# connectors_headers_LEDs.net
KiCad netlist of a schematic drawn in Altium Designer
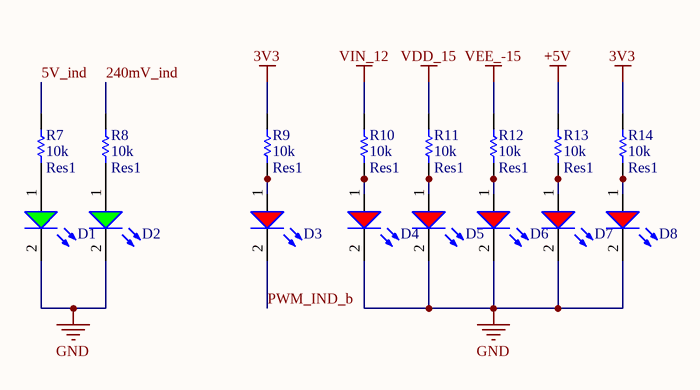
[diagram p0: connectors_headers_LEDs.SchDoc]

(export (version "E")
  (design (tool "Eeschema 10.0.6"))
  (components
    (comp (ref "D1")
      (value "Bright Green, 2.1V, 40°")
      (footprint "WL-TMRC_D3.95H5.3")
      (description "WL-TMRC Mono-color Round Color, THT, D3.95 x H5.3mm, Bright Green, 2.1V, 40°")
      (fields
        (field (name "MANUFACTURER PART NUMBER") "151031VS04000")
        (field (name "MANUFACTURER") "Wurth Elektronik")
      )
      (libsource (lib "Altium_LED_WL-TMRC") (part "151031VS04000"))
    )
    (comp (ref "D2")
      (value "Bright Green, 2.1V, 40°")
      (footprint "WL-TMRC_D3.95H5.3")
      (description "WL-TMRC Mono-color Round Color, THT, D3.95 x H5.3mm, Bright Green, 2.1V, 40°")
      (fields
        (field (name "MANUFACTURER PART NUMBER") "151031VS04000")
        (field (name "MANUFACTURER") "Wurth Elektronik")
      )
      (libsource (lib "Altium_LED_WL-TMRC") (part "151031VS04000"))
    )
    (comp (ref "D3")
      (value "Super Red, 2V, 40°")
      (footprint "WL-TMRC_D3.95H5.3")
      (description "WL-TMRC Mono-color Round Color, THT, D3.95 x H5.3mm, Super Red, 2V, 40°")
      (fields
        (field (name "MANUFACTURER PART NUMBER") "151031SS04000")
        (field (name "MANUFACTURER") "Wurth Elektronik")
      )
      (libsource (lib "Altium_LED_WL-TMRC") (part "151031SS04000"))
    )
    (comp (ref "D4")
      (value "Super Red, 2V, 40°")
      (footprint "WL-TMRC_D3.95H5.3")
      (description "WL-TMRC Mono-color Round Color, THT, D3.95 x H5.3mm, Super Red, 2V, 40°")
      (fields
        (field (name "MANUFACTURER PART NUMBER") "151031SS04000")
        (field (name "MANUFACTURER") "Wurth Elektronik")
      )
      (libsource (lib "Altium_LED_WL-TMRC") (part "151031SS04000"))
    )
    (comp (ref "D5")
      (value "Super Red, 2V, 40°")
      (footprint "WL-TMRC_D3.95H5.3")
      (description "WL-TMRC Mono-color Round Color, THT, D3.95 x H5.3mm, Super Red, 2V, 40°")
      (fields
        (field (name "MANUFACTURER PART NUMBER") "151031SS04000")
        (field (name "MANUFACTURER") "Wurth Elektronik")
      )
      (libsource (lib "Altium_LED_WL-TMRC") (part "151031SS04000"))
    )
    (comp (ref "D6")
      (value "Super Red, 2V, 40°")
      (footprint "WL-TMRC_D3.95H5.3")
      (description "WL-TMRC Mono-color Round Color, THT, D3.95 x H5.3mm, Super Red, 2V, 40°")
      (fields
        (field (name "MANUFACTURER PART NUMBER") "151031SS04000")
        (field (name "MANUFACTURER") "Wurth Elektronik")
      )
      (libsource (lib "Altium_LED_WL-TMRC") (part "151031SS04000"))
    )
    (comp (ref "D7")
      (value "Super Red, 2V, 40°")
      (footprint "WL-TMRC_D3.95H5.3")
      (description "WL-TMRC Mono-color Round Color, THT, D3.95 x H5.3mm, Super Red, 2V, 40°")
      (fields
        (field (name "MANUFACTURER PART NUMBER") "151031SS04000")
        (field (name "MANUFACTURER") "Wurth Elektronik")
      )
      (libsource (lib "Altium_LED_WL-TMRC") (part "151031SS04000"))
    )
    (comp (ref "D8")
      (value "Super Red, 2V, 40°")
      (footprint "WL-TMRC_D3.95H5.3")
      (description "WL-TMRC Mono-color Round Color, THT, D3.95 x H5.3mm, Super Red, 2V, 40°")
      (fields
        (field (name "MANUFACTURER PART NUMBER") "151031SS04000")
        (field (name "MANUFACTURER") "Wurth Elektronik")
      )
      (libsource (lib "Altium_LED_WL-TMRC") (part "151031SS04000"))
    )
    (comp (ref "R7")
      (value "Res1")
      (footprint "AXIAL-0.4")
      (description "Resistor")
      (fields (field (name "ALTIUM_VALUE") "10k") (field (name "PUBLISHER") "Altium Limited"))
      (libsource (lib "Miscellaneous Devices") (part "Res1"))
    )
    (comp (ref "R8")
      (value "Res1")
      (footprint "AXIAL-0.4")
      (description "Resistor")
      (fields (field (name "ALTIUM_VALUE") "10k") (field (name "PUBLISHER") "Altium Limited"))
      (libsource (lib "Miscellaneous Devices") (part "Res1"))
    )
    (comp (ref "R9")
      (value "Res1")
      (footprint "AXIAL-0.4")
      (description "Resistor")
      (fields (field (name "ALTIUM_VALUE") "10k") (field (name "PUBLISHER") "Altium Limited"))
      (libsource (lib "Miscellaneous Devices") (part "Res1"))
    )
    (comp (ref "R10")
      (value "Res1")
      (footprint "AXIAL-0.4")
      (description "Resistor")
      (fields (field (name "ALTIUM_VALUE") "10k") (field (name "PUBLISHER") "Altium Limited"))
      (libsource (lib "Miscellaneous Devices") (part "Res1"))
    )
    (comp (ref "R11")
      (value "Res1")
      (footprint "AXIAL-0.4")
      (description "Resistor")
      (fields (field (name "ALTIUM_VALUE") "10k") (field (name "PUBLISHER") "Altium Limited"))
      (libsource (lib "Miscellaneous Devices") (part "Res1"))
    )
    (comp (ref "R12")
      (value "Res1")
      (footprint "AXIAL-0.4")
      (description "Resistor")
      (fields (field (name "ALTIUM_VALUE") "10k") (field (name "PUBLISHER") "Altium Limited"))
      (libsource (lib "Miscellaneous Devices") (part "Res1"))
    )
    (comp (ref "R13")
      (value "Res1")
      (footprint "AXIAL-0.4")
      (description "Resistor")
      (fields (field (name "ALTIUM_VALUE") "10k") (field (name "PUBLISHER") "Altium Limited"))
      (libsource (lib "Miscellaneous Devices") (part "Res1"))
    )
    (comp (ref "R14")
      (value "Res1")
      (footprint "AXIAL-0.4")
      (description "Resistor")
      (fields (field (name "ALTIUM_VALUE") "10k") (field (name "PUBLISHER") "Altium Limited"))
      (libsource (lib "Miscellaneous Devices") (part "Res1"))
    )
  )
  (nets
    (net (code "1") (name "+5V") (class "Default")
      (node (ref "R13") (pin "2") (pinfunction "2_2") (pintype "passive"))
    )
    (net (code "2") (name "/5V_ind") (class "Default")
      (node (ref "R7") (pin "2") (pinfunction "2_2") (pintype "passive"))
    )
    (net (code "3") (name "/240mV_ind") (class "Default")
      (node (ref "R8") (pin "2") (pinfunction "2_2") (pintype "passive"))
    )
    (net (code "4") (name "/PWM_IND_b") (class "Default")
      (node (ref "D3") (pin "2") (pinfunction "K_2") (pintype "passive"))
    )
    (net (code "5") (name "3V3") (class "Default")
      (node (ref "R14") (pin "2") (pinfunction "2_2") (pintype "passive"))
      (node (ref "R9") (pin "2") (pinfunction "2_2") (pintype "passive"))
    )
    (net (code "6") (name "GND") (class "Default")
      (node (ref "D1") (pin "2") (pinfunction "K_2") (pintype "passive"))
      (node (ref "D2") (pin "2") (pinfunction "K_2") (pintype "passive"))
      (node (ref "D4") (pin "2") (pinfunction "K_2") (pintype "passive"))
      (node (ref "D5") (pin "2") (pinfunction "K_2") (pintype "passive"))
      (node (ref "D6") (pin "2") (pinfunction "K_2") (pintype "passive"))
      (node (ref "D7") (pin "2") (pinfunction "K_2") (pintype "passive"))
      (node (ref "D8") (pin "2") (pinfunction "K_2") (pintype "passive"))
    )
    (net (code "7") (name "Net-(D1-A)") (class "Default")
      (node (ref "D1") (pin "1") (pinfunction "A_1") (pintype "passive"))
      (node (ref "R7") (pin "1") (pinfunction "1_1") (pintype "passive"))
    )
    (net (code "8") (name "Net-(D2-A)") (class "Default")
      (node (ref "D2") (pin "1") (pinfunction "A_1") (pintype "passive"))
      (node (ref "R8") (pin "1") (pinfunction "1_1") (pintype "passive"))
    )
    (net (code "9") (name "Net-(D3-A)") (class "Default")
      (node (ref "D3") (pin "1") (pinfunction "A_1") (pintype "passive"))
      (node (ref "R9") (pin "1") (pinfunction "1_1") (pintype "passive"))
    )
    (net (code "10") (name "Net-(D4-A)") (class "Default")
      (node (ref "D4") (pin "1") (pinfunction "A_1") (pintype "passive"))
      (node (ref "R10") (pin "1") (pinfunction "1_1") (pintype "passive"))
    )
    (net (code "11") (name "Net-(D5-A)") (class "Default")
      (node (ref "D5") (pin "1") (pinfunction "A_1") (pintype "passive"))
      (node (ref "R11") (pin "1") (pinfunction "1_1") (pintype "passive"))
    )
    (net (code "12") (name "Net-(D6-A)") (class "Default")
      (node (ref "D6") (pin "1") (pinfunction "A_1") (pintype "passive"))
      (node (ref "R12") (pin "1") (pinfunction "1_1") (pintype "passive"))
    )
    (net (code "13") (name "Net-(D7-A)") (class "Default")
      (node (ref "D7") (pin "1") (pinfunction "A_1") (pintype "passive"))
      (node (ref "R13") (pin "1") (pinfunction "1_1") (pintype "passive"))
    )
    (net (code "14") (name "Net-(D8-A)") (class "Default")
      (node (ref "D8") (pin "1") (pinfunction "A_1") (pintype "passive"))
      (node (ref "R14") (pin "1") (pinfunction "1_1") (pintype "passive"))
    )
    (net (code "15") (name "VDD_15") (class "Default")
      (node (ref "R11") (pin "2") (pinfunction "2_2") (pintype "passive"))
    )
    (net (code "16") (name "VEE_-15") (class "Default")
      (node (ref "R12") (pin "2") (pinfunction "2_2") (pintype "passive"))
    )
    (net (code "17") (name "VIN_12") (class "Default")
      (node (ref "R10") (pin "2") (pinfunction "2_2") (pintype "passive"))
    )
  )
)
